# Sheet6.net
KiCad netlist of a schematic drawn in Altium Designer
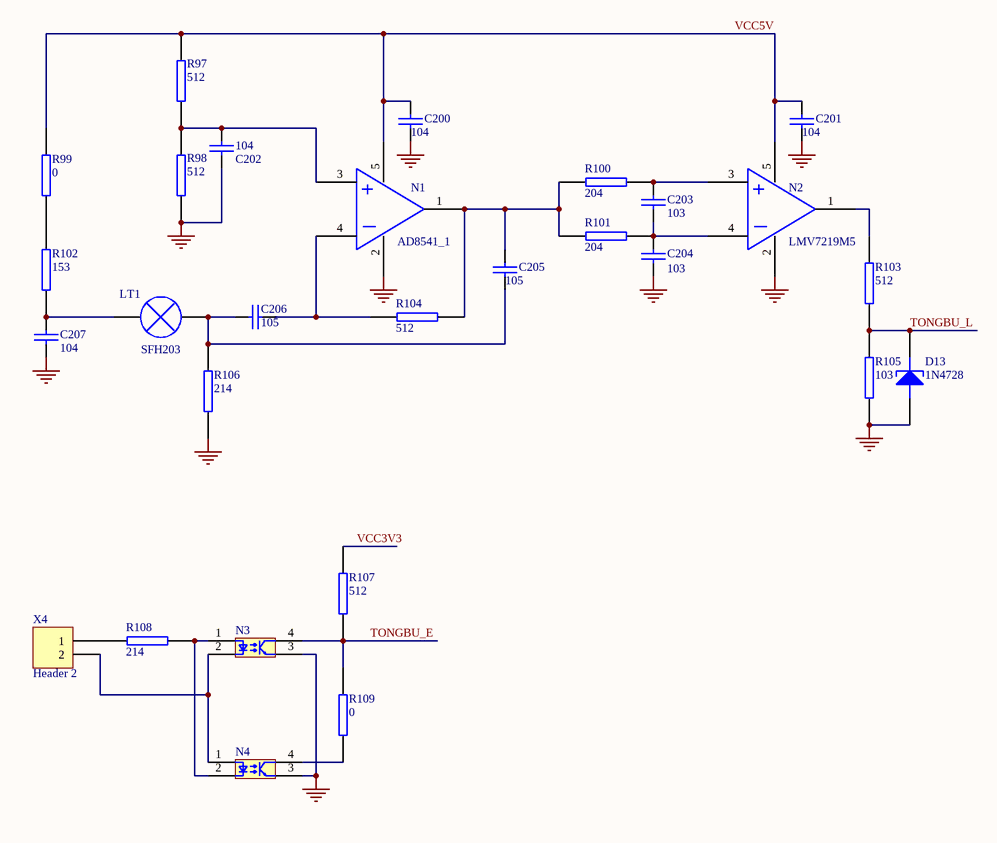
[diagram p0: Sheet6.SchDoc]

(export (version "E")
  (design (tool "Eeschema 10.0.6"))
  (components
    (comp (ref "C200")
      (value "104")
      (footprint "0603")
      (description "Capacitor")
      (libsource (lib "*") (part "CAP"))
    )
    (comp (ref "C201")
      (value "104")
      (footprint "0603")
      (description "Capacitor")
      (libsource (lib "*") (part "CAP"))
    )
    (comp (ref "C202")
      (value "104")
      (footprint "0603")
      (description "Capacitor")
      (libsource (lib "*") (part "CAP"))
    )
    (comp (ref "C203")
      (value "103")
      (footprint "0603")
      (description "Capacitor")
      (libsource (lib "*") (part "CAP"))
    )
    (comp (ref "C204")
      (value "103")
      (footprint "0603")
      (description "Capacitor")
      (libsource (lib "*") (part "CAP"))
    )
    (comp (ref "C205")
      (value "105")
      (footprint "0603")
      (description "Capacitor")
      (libsource (lib "*") (part "CAP"))
    )
    (comp (ref "C206")
      (value "105")
      (footprint "0603")
      (description "Capacitor")
      (libsource (lib "*") (part "CAP"))
    )
    (comp (ref "C207")
      (value "104")
      (footprint "0603")
      (description "Capacitor")
      (libsource (lib "*") (part "CAP"))
    )
    (comp (ref "D13")
      (value "1N4728")
      (footprint "M7")
      (description "Diode Tunnel")
      (libsource (lib "*") (part "DIODE TUNNEL"))
    )
    (comp (ref "LT1") (value "SFH203") (footprint "LED5") (libsource (lib "*") (part "LAMP")))
    (comp (ref "N1") (value "AD8541_1") (footprint "SOT-23-5") (libsource (lib "*") (part "OPA")))
    (comp (ref "N2") (value "LMV7219M5") (footprint "SOT-23-5") (libsource (lib "*") (part "OPA")))
    (comp (ref "N3") (value "TLP281-1(SOC4)") (footprint "TLP821-1") (libsource (lib "*") (part "TLP521-1")))
    (comp (ref "N4") (value "TLP281-1(SOC4)") (footprint "TLP821-1") (libsource (lib "*") (part "TLP521-1")))
    (comp (ref "R97") (value "512") (footprint "0603") (libsource (lib "*") (part "RES2")))
    (comp (ref "R98") (value "512") (footprint "0603") (libsource (lib "*") (part "RES2")))
    (comp (ref "R99") (value "0") (footprint "0603") (libsource (lib "*") (part "RES2")))
    (comp (ref "R100") (value "204") (footprint "0603") (libsource (lib "*") (part "RES2")))
    (comp (ref "R101") (value "204") (footprint "0603") (libsource (lib "*") (part "RES2")))
    (comp (ref "R102") (value "153") (footprint "0603") (libsource (lib "*") (part "RES2")))
    (comp (ref "R103") (value "512") (footprint "0603") (libsource (lib "*") (part "RES2")))
    (comp (ref "R104") (value "512") (footprint "0603") (libsource (lib "*") (part "RES2")))
    (comp (ref "R105") (value "103") (footprint "0603") (libsource (lib "*") (part "RES2")))
    (comp (ref "R106") (value "214") (footprint "0603") (libsource (lib "*") (part "RES2")))
    (comp (ref "R107") (value "512") (footprint "0603") (libsource (lib "*") (part "RES2")))
    (comp (ref "R108") (value "214") (footprint "AXIAL-0.4") (libsource (lib "*") (part "RES2")))
    (comp (ref "R109") (value "0") (footprint "0603") (libsource (lib "*") (part "RES2")))
    (comp (ref "X4")
      (value "Header 2")
      (footprint "SIP2X")
      (description "Header, 2-Pin")
      (fields (field (name "PUBLISHER") "Altium Limited"))
      (libsource (lib "Miscellaneous Connectors") (part "Header 2"))
    )
  )
  (nets
    (net (code "1") (name "/TONGBU_E") (class "Default")
      (node (ref "N3") (pin "4") (pinfunction "4_4") (pintype "passive"))
      (node (ref "R107") (pin "1") (pinfunction "1_1") (pintype "passive"))
      (node (ref "R109") (pin "2") (pinfunction "2_2") (pintype "passive"))
    )
    (net (code "2") (name "/TONGBU_L") (class "Default")
      (node (ref "D13") (pin "2") (pinfunction "K_2") (pintype "passive"))
      (node (ref "R103") (pin "1") (pinfunction "1_1") (pintype "passive"))
      (node (ref "R105") (pin "2") (pinfunction "2_2") (pintype "passive"))
    )
    (net (code "3") (name "/VCC3V3") (class "Default")
      (node (ref "R107") (pin "2") (pinfunction "2_2") (pintype "passive"))
    )
    (net (code "4") (name "/VCC5V") (class "Default")
      (node (ref "C200") (pin "1") (pinfunction "1_1") (pintype "passive"))
      (node (ref "C201") (pin "1") (pinfunction "1_1") (pintype "passive"))
      (node (ref "N1") (pin "5") (pintype "passive"))
      (node (ref "N2") (pin "5") (pintype "passive"))
      (node (ref "R97") (pin "2") (pinfunction "2_2") (pintype "passive"))
      (node (ref "R99") (pin "2") (pinfunction "2_2") (pintype "passive"))
    )
    (net (code "5") (name "GND") (class "Default")
      (node (ref "C200") (pin "2") (pinfunction "2_2") (pintype "passive"))
      (node (ref "C201") (pin "2") (pinfunction "2_2") (pintype "passive"))
      (node (ref "C202") (pin "2") (pinfunction "2_2") (pintype "passive"))
      (node (ref "C204") (pin "2") (pinfunction "2_2") (pintype "passive"))
      (node (ref "C207") (pin "2") (pinfunction "2_2") (pintype "passive"))
      (node (ref "D13") (pin "1") (pinfunction "A_1") (pintype "passive"))
      (node (ref "N1") (pin "2") (pintype "passive"))
      (node (ref "N2") (pin "2") (pintype "passive"))
      (node (ref "N3") (pin "3") (pinfunction "3_3") (pintype "passive"))
      (node (ref "N4") (pin "3") (pinfunction "3_3") (pintype "passive"))
      (node (ref "R105") (pin "1") (pinfunction "1_1") (pintype "passive"))
      (node (ref "R106") (pin "2") (pinfunction "2_2") (pintype "passive"))
      (node (ref "R98") (pin "1") (pinfunction "1_1") (pintype "passive"))
    )
    (net (code "6") (name "Net-(C202-Pad1)") (class "Default")
      (node (ref "C202") (pin "1") (pinfunction "1_1") (pintype "passive"))
      (node (ref "N1") (pin "3") (pintype "passive"))
      (node (ref "R97") (pin "1") (pinfunction "1_1") (pintype "passive"))
      (node (ref "R98") (pin "2") (pinfunction "2_2") (pintype "passive"))
    )
    (net (code "7") (name "Net-(C203-Pad1)") (class "Default")
      (node (ref "C203") (pin "1") (pinfunction "1_1") (pintype "passive"))
      (node (ref "N2") (pin "3") (pintype "passive"))
      (node (ref "R100") (pin "2") (pinfunction "2_2") (pintype "passive"))
    )
    (net (code "8") (name "Net-(C203-Pad2)") (class "Default")
      (node (ref "C203") (pin "2") (pinfunction "2_2") (pintype "passive"))
      (node (ref "C204") (pin "1") (pinfunction "1_1") (pintype "passive"))
      (node (ref "N2") (pin "4") (pintype "passive"))
      (node (ref "R101") (pin "2") (pinfunction "2_2") (pintype "passive"))
    )
    (net (code "9") (name "Net-(C205-Pad1)") (class "Default")
      (node (ref "C205") (pin "1") (pinfunction "1_1") (pintype "passive"))
      (node (ref "N1") (pin "1") (pintype "passive"))
      (node (ref "R100") (pin "1") (pinfunction "1_1") (pintype "passive"))
      (node (ref "R101") (pin "1") (pinfunction "1_1") (pintype "passive"))
      (node (ref "R104") (pin "1") (pinfunction "1_1") (pintype "passive"))
    )
    (net (code "10") (name "Net-(C205-Pad2)") (class "Default")
      (node (ref "C205") (pin "2") (pinfunction "2_2") (pintype "passive"))
      (node (ref "C206") (pin "1") (pinfunction "1_1") (pintype "passive"))
      (node (ref "LT1") (pin "2") (pinfunction "2_2") (pintype "passive"))
      (node (ref "R106") (pin "1") (pinfunction "1_1") (pintype "passive"))
    )
    (net (code "11") (name "Net-(C206-Pad2)") (class "Default")
      (node (ref "C206") (pin "2") (pinfunction "2_2") (pintype "passive"))
      (node (ref "N1") (pin "4") (pintype "passive"))
      (node (ref "R104") (pin "2") (pinfunction "2_2") (pintype "passive"))
    )
    (net (code "12") (name "Net-(C207-Pad1)") (class "Default")
      (node (ref "C207") (pin "1") (pinfunction "1_1") (pintype "passive"))
      (node (ref "LT1") (pin "1") (pinfunction "1_1") (pintype "passive"))
      (node (ref "R102") (pin "1") (pinfunction "1_1") (pintype "passive"))
    )
    (net (code "13") (name "Net-(N2-Pad1)") (class "Default")
      (node (ref "N2") (pin "1") (pintype "passive"))
      (node (ref "R103") (pin "2") (pinfunction "2_2") (pintype "passive"))
    )
    (net (code "14") (name "Net-(N3-Pad1)") (class "Default")
      (node (ref "N3") (pin "1") (pinfunction "1_1") (pintype "passive"))
      (node (ref "N4") (pin "2") (pinfunction "2_2") (pintype "passive"))
      (node (ref "R108") (pin "2") (pinfunction "2_2") (pintype "passive"))
    )
    (net (code "15") (name "Net-(N3-Pad2)") (class "Default")
      (node (ref "N3") (pin "2") (pinfunction "2_2") (pintype "passive"))
      (node (ref "N4") (pin "1") (pinfunction "1_1") (pintype "passive"))
      (node (ref "X4") (pin "2") (pinfunction "2_2") (pintype "passive"))
    )
    (net (code "16") (name "Net-(N4-Pad4)") (class "Default")
      (node (ref "N4") (pin "4") (pinfunction "4_4") (pintype "passive"))
      (node (ref "R109") (pin "1") (pinfunction "1_1") (pintype "passive"))
    )
    (net (code "17") (name "Net-(R102-Pad2)") (class "Default")
      (node (ref "R102") (pin "2") (pinfunction "2_2") (pintype "passive"))
      (node (ref "R99") (pin "1") (pinfunction "1_1") (pintype "passive"))
    )
    (net (code "18") (name "Net-(R108-Pad1)") (class "Default")
      (node (ref "R108") (pin "1") (pinfunction "1_1") (pintype "passive"))
      (node (ref "X4") (pin "1") (pinfunction "1_1") (pintype "passive"))
    )
  )
)
